# Sheet1.net
KiCad netlist of a schematic drawn in Altium Designer
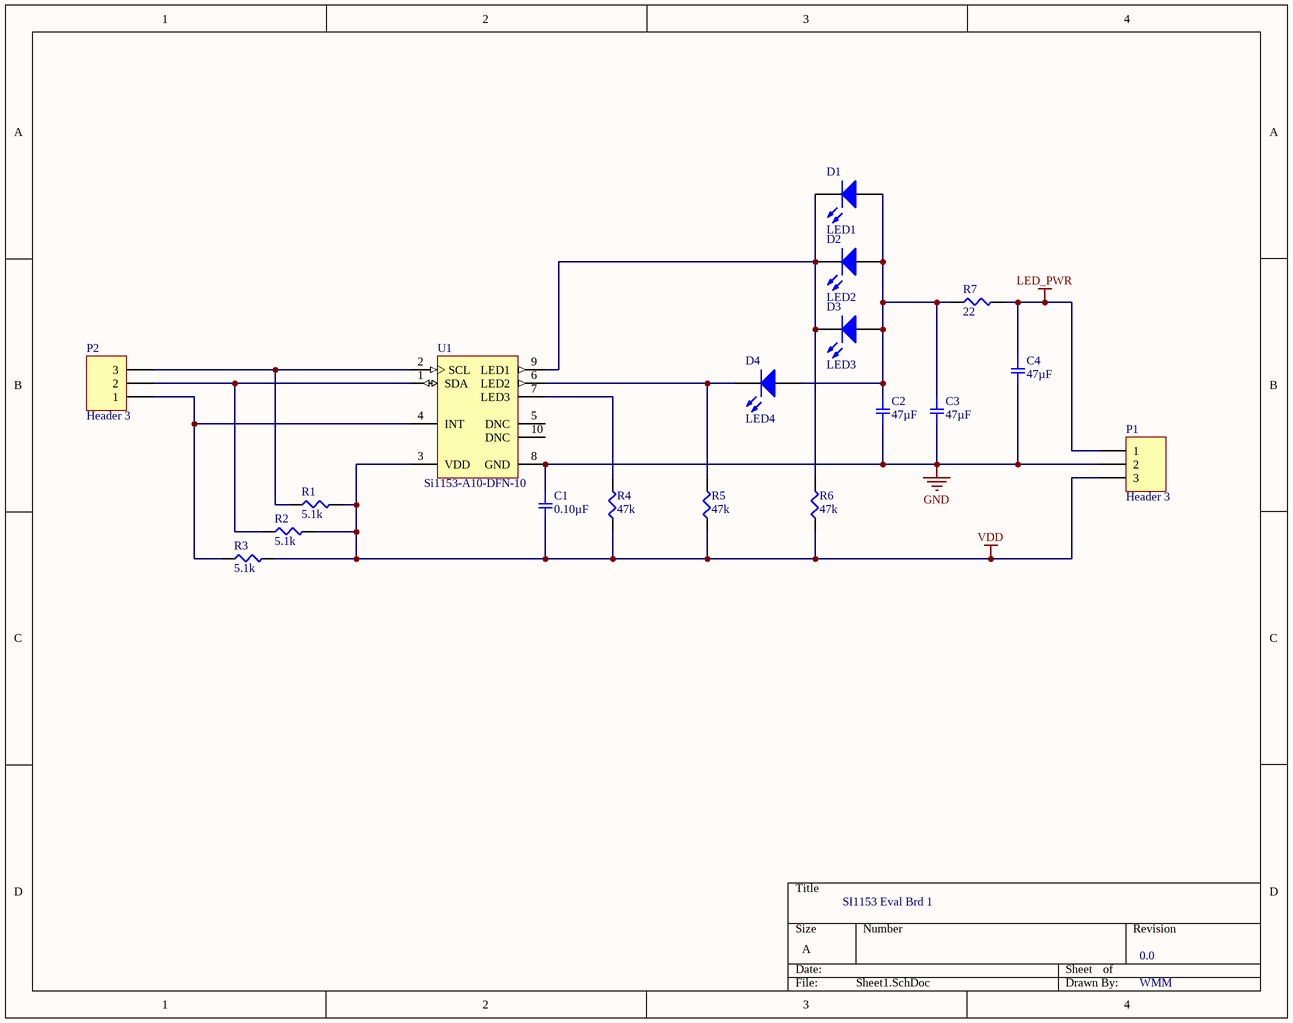
[diagram p0: Sheet1.SchDoc]

(export (version "E")
  (design (tool "Eeschema 10.0.6"))
  (components
    (comp (ref "C1")
      (value "0.10µF")
      (footprint "SMD-0402C")
      (description "CAP CER 0.1UF 16V X7R 0402")
      (fields
        (field (name "DIGI-KEY PART NUMBER") "490-4759-1-ND")
        (field (name "PART NUMBER") "GCM155R71C104KA55D")
      )
      (libsource (lib "capacitor_murata_0402") (part "GCM155R71C104KA55D"))
    )
    (comp (ref "C2")
      (value "47µF")
      (footprint "SMD-0603C")
      (description "CAP CER 47UF 6.3V X5R 0603")
      (fields
        (field (name "DIGI-KEY PART NUMBER") "490-13255-1-ND")
        (field (name "PART NUMBER") "ZRB18AR60J476ME01L")
      )
      (libsource (lib "capacitor_murata_0603") (part "ZRB18AR60J476ME01L"))
    )
    (comp (ref "C3")
      (value "47µF")
      (footprint "SMD-0603C")
      (description "CAP CER 47UF 6.3V X5R 0603")
      (fields
        (field (name "DIGI-KEY PART NUMBER") "490-13255-1-ND")
        (field (name "PART NUMBER") "ZRB18AR60J476ME01L")
      )
      (libsource (lib "capacitor_murata_0603") (part "ZRB18AR60J476ME01L"))
    )
    (comp (ref "C4")
      (value "47µF")
      (footprint "SMD-0603C")
      (description "CAP CER 47UF 6.3V X5R 0603")
      (fields
        (field (name "DIGI-KEY PART NUMBER") "490-13255-1-ND")
        (field (name "PART NUMBER") "ZRB18AR60J476ME01L")
      )
      (libsource (lib "capacitor_murata_0603") (part "ZRB18AR60J476ME01L"))
    )
    (comp (ref "D1")
      (value "LED1")
      (footprint "3.5X2.8X1.9")
      (description "Typical BLUE SiC LED")
      (fields (field (name "PUBLISHER") "Altium Limited"))
      (libsource (lib "Miscellaneous Devices") (part "LED3"))
    )
    (comp (ref "D2")
      (value "LED2")
      (footprint "3.5X2.8X1.9")
      (description "Typical BLUE SiC LED")
      (fields (field (name "PUBLISHER") "Altium Limited"))
      (libsource (lib "Miscellaneous Devices") (part "LED3"))
    )
    (comp (ref "D3")
      (value "LED3")
      (footprint "3.5X2.8X1.9")
      (description "Typical BLUE SiC LED")
      (fields (field (name "PUBLISHER") "Altium Limited"))
      (libsource (lib "Miscellaneous Devices") (part "LED3"))
    )
    (comp (ref "D4")
      (value "LED4")
      (footprint "3.5X2.8X1.9")
      (description "Typical BLUE SiC LED")
      (fields (field (name "PUBLISHER") "Altium Limited"))
      (libsource (lib "Miscellaneous Devices") (part "LED3"))
    )
    (comp (ref "P1")
      (value "Header 3")
      (footprint "HDR1X3")
      (description "Header, 3-Pin")
      (fields (field (name "PUBLISHER") "Altium Limited"))
      (libsource (lib "") (part "Header 3_1"))
    )
    (comp (ref "P2")
      (value "Header 3")
      (footprint "HDR1X3")
      (description "Header, 3-Pin")
      (fields (field (name "PUBLISHER") "Altium Limited"))
      (libsource (lib "Miscellaneous Connectors") (part "Header 3"))
    )
    (comp (ref "R1")
      (value "5.1k")
      (footprint "SMD-0402-RES")
      (description "RES SMD 5.1K OHM 5% 1/10W 0402")
      (fields (field (name "PART NUMBER") "ERJ-2GEJ512X") (field (name "DIGI-KEY PART NUMBER") "P5.1KJCT-ND"))
      (libsource (lib "Panasonic_ERJ_0402") (part "ERJ-2GEJ512X"))
    )
    (comp (ref "R2")
      (value "5.1k")
      (footprint "SMD-0402-RES")
      (description "RES SMD 5.1K OHM 5% 1/10W 0402")
      (fields (field (name "PART NUMBER") "ERJ-2GEJ512X") (field (name "DIGI-KEY PART NUMBER") "P5.1KJCT-ND"))
      (libsource (lib "Panasonic_ERJ_0402") (part "ERJ-2GEJ512X"))
    )
    (comp (ref "R3")
      (value "5.1k")
      (footprint "SMD-0402-RES")
      (description "RES SMD 5.1K OHM 5% 1/10W 0402")
      (fields (field (name "PART NUMBER") "ERJ-2GEJ512X") (field (name "DIGI-KEY PART NUMBER") "P5.1KJCT-ND"))
      (libsource (lib "Panasonic_ERJ_0402") (part "ERJ-2GEJ512X"))
    )
    (comp (ref "R4")
      (value "47k")
      (footprint "SMD-0402-RES")
      (description "RES SMD 47K OHM 5% 1/10W 0402")
      (fields (field (name "PART NUMBER") "ERJ-2GEJ473X") (field (name "DIGI-KEY PART NUMBER") "P47KJCT-ND"))
      (libsource (lib "Panasonic_ERJ_0402") (part "ERJ-2GEJ473X"))
    )
    (comp (ref "R5")
      (value "47k")
      (footprint "SMD-0402-RES")
      (description "RES SMD 47K OHM 5% 1/10W 0402")
      (fields (field (name "PART NUMBER") "ERJ-2GEJ473X") (field (name "DIGI-KEY PART NUMBER") "P47KJCT-ND"))
      (libsource (lib "Panasonic_ERJ_0402") (part "ERJ-2GEJ473X"))
    )
    (comp (ref "R6")
      (value "47k")
      (footprint "SMD-0402-RES")
      (description "RES SMD 47K OHM 5% 1/10W 0402")
      (fields (field (name "PART NUMBER") "ERJ-2GEJ473X") (field (name "DIGI-KEY PART NUMBER") "P47KJCT-ND"))
      (libsource (lib "Panasonic_ERJ_0402") (part "ERJ-2GEJ473X"))
    )
    (comp (ref "R7")
      (value "22")
      (footprint "SMD-0402-RES")
      (description "RES SMD 22 OHM 5% 1/10W 0402")
      (fields (field (name "PART NUMBER") "ERJ-2GEJ220X") (field (name "DIGI-KEY PART NUMBER") "P22JCT-ND"))
      (libsource (lib "Panasonic_ERJ_0402") (part "ERJ-2GEJ220X"))
    )
    (comp (ref "U1")
      (value "Si1153-A10-DFN-10")
      (footprint "SLAB-QFN-10_V")
      (fields (field (name "MANUFACTURER") "Silicon Labs") (field (name "PARTNUMBER") "Si1143-A10-GMR"))
      (libsource (lib "Silicon Labs Sensors") (part "Si1143-A10-GMR"))
    )
  )
  (nets
    (net (code "1") (name "GND") (class "Default")
      (node (ref "C1") (pin "1") (pinfunction "1_1") (pintype "passive"))
      (node (ref "C2") (pin "2") (pinfunction "2_2") (pintype "passive"))
      (node (ref "C3") (pin "2") (pinfunction "2_2") (pintype "passive"))
      (node (ref "C4") (pin "2") (pinfunction "2_2") (pintype "passive"))
      (node (ref "P1") (pin "2") (pinfunction "2_2") (pintype "passive"))
      (node (ref "U1") (pin "8") (pinfunction "GND_8") (pintype "power_in"))
    )
    (net (code "2") (name "LED_PWR") (class "Default")
      (node (ref "C4") (pin "1") (pinfunction "1_1") (pintype "passive"))
      (node (ref "P1") (pin "1") (pinfunction "1_1") (pintype "passive"))
      (node (ref "R7") (pin "2") (pinfunction "2_2") (pintype "passive"))
    )
    (net (code "3") (name "Net-(D1-A)") (class "Default")
      (node (ref "C2") (pin "1") (pinfunction "1_1") (pintype "passive"))
      (node (ref "C3") (pin "1") (pinfunction "1_1") (pintype "passive"))
      (node (ref "D1") (pin "1") (pinfunction "A_1") (pintype "passive"))
      (node (ref "D2") (pin "1") (pinfunction "A_1") (pintype "passive"))
      (node (ref "D3") (pin "1") (pinfunction "A_1") (pintype "passive"))
      (node (ref "D4") (pin "1") (pinfunction "A_1") (pintype "passive"))
      (node (ref "R7") (pin "1") (pinfunction "1_1") (pintype "passive"))
    )
    (net (code "4") (name "Net-(D1-K)") (class "Default")
      (node (ref "D1") (pin "2") (pinfunction "K_2") (pintype "passive"))
      (node (ref "D2") (pin "2") (pinfunction "K_2") (pintype "passive"))
      (node (ref "D3") (pin "2") (pinfunction "K_2") (pintype "passive"))
      (node (ref "R6") (pin "2") (pinfunction "2_2") (pintype "passive"))
      (node (ref "U1") (pin "9") (pinfunction "LED1_9") (pintype "output"))
    )
    (net (code "5") (name "Net-(D4-K)") (class "Default")
      (node (ref "D4") (pin "2") (pinfunction "K_2") (pintype "passive"))
      (node (ref "R5") (pin "2") (pinfunction "2_2") (pintype "passive"))
      (node (ref "U1") (pin "6") (pinfunction "LED2_6") (pintype "output"))
    )
    (net (code "6") (name "Net-(U1-INT)") (class "Default")
      (node (ref "P2") (pin "1") (pinfunction "1_1") (pintype "passive"))
      (node (ref "R3") (pin "1") (pinfunction "1_1") (pintype "passive"))
      (node (ref "U1") (pin "4") (pinfunction "INT_4") (pintype "open_collector"))
    )
    (net (code "7") (name "Net-(U1-LED3)") (class "Default")
      (node (ref "R4") (pin "2") (pinfunction "2_2") (pintype "passive"))
      (node (ref "U1") (pin "7") (pinfunction "LED3_7") (pintype "passive"))
    )
    (net (code "8") (name "Net-(U1-SCL)") (class "Default")
      (node (ref "P2") (pin "3") (pinfunction "3_3") (pintype "passive"))
      (node (ref "R1") (pin "1") (pinfunction "1_1") (pintype "passive"))
      (node (ref "U1") (pin "2") (pinfunction "SCL_2") (pintype "input"))
    )
    (net (code "9") (name "Net-(U1-SDA)") (class "Default")
      (node (ref "P2") (pin "2") (pinfunction "2_2") (pintype "passive"))
      (node (ref "R2") (pin "1") (pinfunction "1_1") (pintype "passive"))
      (node (ref "U1") (pin "1") (pinfunction "SDA_1") (pintype "bidirectional"))
    )
    (net (code "10") (name "VDD") (class "Default")
      (node (ref "C1") (pin "2") (pinfunction "2_2") (pintype "passive"))
      (node (ref "P1") (pin "3") (pinfunction "3_3") (pintype "passive"))
      (node (ref "R1") (pin "2") (pinfunction "2_2") (pintype "passive"))
      (node (ref "R2") (pin "2") (pinfunction "2_2") (pintype "passive"))
      (node (ref "R3") (pin "2") (pinfunction "2_2") (pintype "passive"))
      (node (ref "R4") (pin "1") (pinfunction "1_1") (pintype "passive"))
      (node (ref "R5") (pin "1") (pinfunction "1_1") (pintype "passive"))
      (node (ref "R6") (pin "1") (pinfunction "1_1") (pintype "passive"))
      (node (ref "U1") (pin "3") (pinfunction "VDD_3") (pintype "power_in"))
    )
    (net (code "11") (name "unconnected-(U1-DNC-Pad5)") (class "Default")
      (node (ref "U1") (pin "5") (pinfunction "DNC_5") (pintype "passive"))
    )
    (net (code "12") (name "unconnected-(U1-DNC-Pad10)") (class "Default")
      (node (ref "U1") (pin "10") (pinfunction "DNC_10") (pintype "passive"))
    )
  )
)
